# CW340_FPGA_XADC.net
KiCad netlist of a schematic drawn in Altium Designer
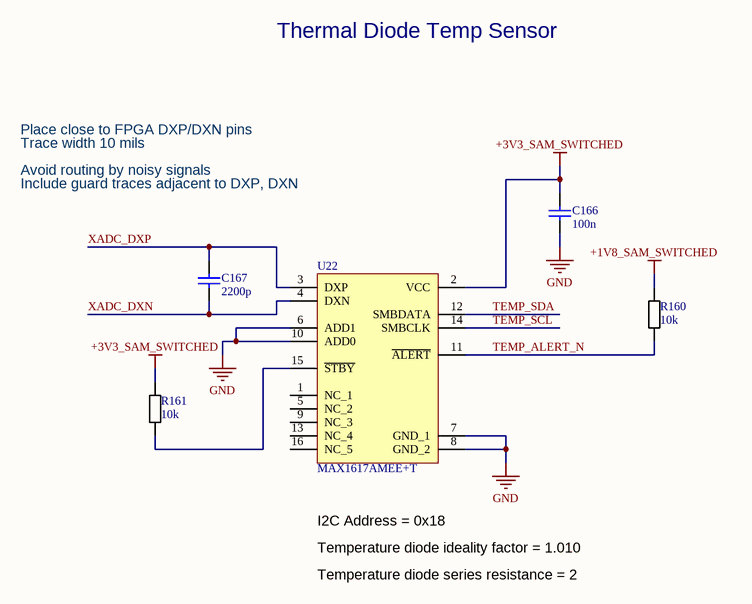
[diagram p0: CW340_FPGA_XADC.SchDoc]

(export (version "E")
  (design (tool "Eeschema 10.0.6"))
  (components
    (comp (ref "C166")
      (value "100n")
      (footprint "CAPC0402_M")
      (description "100n, 0402")
      (fields (field (name "PART NUMBER") "CCHIP-100n-0402"))
      (libsource (lib "NewAE_AltiumLib") (part "CAP"))
    )
    (comp (ref "C167")
      (value "2200p")
      (footprint "CAPC0402_M")
      (description "CAP CER 2200PF 50V X7R 0402")
      (fields (field (name "PART NUMBER") "CCHIP-2200P-0402-50V") (field (name "TOLERANCE") "±10%"))
      (libsource (lib "NewAE_AltiumLib") (part "CAP"))
    )
    (comp (ref "R160")
      (value "10k")
      (footprint "RESC1005X40N")
      (description "10k res, 0402, 1%, 1/16W")
      (fields (field (name "PART NUMBER") "RCHIP-10K-0402") (field (name "TOLERANCE") "1%"))
      (libsource (lib "NewAE_AltiumLib") (part "RES-EU"))
    )
    (comp (ref "R161")
      (value "10k")
      (footprint "RESC1005X40N")
      (description "10k res, 0402, 1%, 1/16W")
      (fields (field (name "PART NUMBER") "RCHIP-10K-0402") (field (name "TOLERANCE") "1%"))
      (libsource (lib "NewAE_AltiumLib") (part "RES-EU"))
    )
    (comp (ref "U22")
      (value "Temp Diode sensor interface")
      (footprint "SOP64P600X175-16N")
      (description "SENSOR DIGITAL -55C-125C 16QSOP")
      (fields
        (field (name "MANUFACTURER PART NUMBER") "MAX1617AMEE+T")
        (field (name "PART NUMBER") "MAX1617AMEE+T")
      )
      (libsource (lib "NewAE_AltiumLib") (part "MAX1617AMEE+T"))
    )
  )
  (nets
    (net (code "1") (name "+1V8_SAM_SWITCHED") (class "Default")
      (node (ref "R160") (pin "1") (pinfunction "1_1") (pintype "passive"))
    )
    (net (code "2") (name "+3V3_SAM_SWITCHED") (class "Default")
      (node (ref "C166") (pin "1") (pinfunction "1_1") (pintype "passive"))
      (node (ref "R161") (pin "1") (pinfunction "1_1") (pintype "passive"))
      (node (ref "U22") (pin "2") (pinfunction "VCC_2") (pintype "passive"))
    )
    (net (code "3") (name "/TEMP_ALERT_N") (class "Default")
      (node (ref "R160") (pin "2") (pinfunction "2_2") (pintype "passive"))
      (node (ref "U22") (pin "11") (pinfunction "ALERT_11") (pintype "passive"))
    )
    (net (code "4") (name "/TEMP_SCL") (class "Default")
      (node (ref "U22") (pin "14") (pinfunction "SMBCLK_14") (pintype "passive"))
    )
    (net (code "5") (name "/TEMP_SDA") (class "Default")
      (node (ref "U22") (pin "12") (pinfunction "SMBDATA_12") (pintype "passive"))
    )
    (net (code "6") (name "/XADC_DXN") (class "Default")
      (node (ref "C167") (pin "2") (pinfunction "2_2") (pintype "passive"))
      (node (ref "U22") (pin "4") (pinfunction "DXN_4") (pintype "passive"))
    )
    (net (code "7") (name "/XADC_DXP") (class "Default")
      (node (ref "C167") (pin "1") (pinfunction "1_1") (pintype "passive"))
      (node (ref "U22") (pin "3") (pinfunction "DXP_3") (pintype "passive"))
    )
    (net (code "8") (name "GND") (class "Default")
      (node (ref "C166") (pin "2") (pinfunction "2_2") (pintype "passive"))
      (node (ref "U22") (pin "10") (pinfunction "ADD0_10") (pintype "passive"))
      (node (ref "U22") (pin "6") (pinfunction "ADD1_6") (pintype "passive"))
      (node (ref "U22") (pin "7") (pinfunction "GND_1_7") (pintype "passive"))
      (node (ref "U22") (pin "8") (pinfunction "GND_2_8") (pintype "passive"))
    )
    (net (code "9") (name "Net-(U22-STBY)") (class "Default")
      (node (ref "R161") (pin "2") (pinfunction "2_2") (pintype "passive"))
      (node (ref "U22") (pin "15") (pinfunction "STBY_15") (pintype "passive"))
    )
    (net (code "10") (name "unconnected-(U22-NC_1-Pad1)") (class "Default")
      (node (ref "U22") (pin "1") (pinfunction "NC_1_1") (pintype "passive"))
    )
    (net (code "11") (name "unconnected-(U22-NC_2-Pad5)") (class "Default")
      (node (ref "U22") (pin "5") (pinfunction "NC_2_5") (pintype "passive"))
    )
    (net (code "12") (name "unconnected-(U22-NC_3-Pad9)") (class "Default")
      (node (ref "U22") (pin "9") (pinfunction "NC_3_9") (pintype "passive"))
    )
    (net (code "13") (name "unconnected-(U22-NC_4-Pad13)") (class "Default")
      (node (ref "U22") (pin "13") (pinfunction "NC_4_13") (pintype "passive"))
    )
    (net (code "14") (name "unconnected-(U22-NC_5-Pad16)") (class "Default")
      (node (ref "U22") (pin "16") (pinfunction "NC_5_16") (pintype "passive"))
    )
  )
)
